# Hardware_Tutorial_-_Controller_Board_Int.net
KiCad netlist of a schematic drawn in Altium Designer
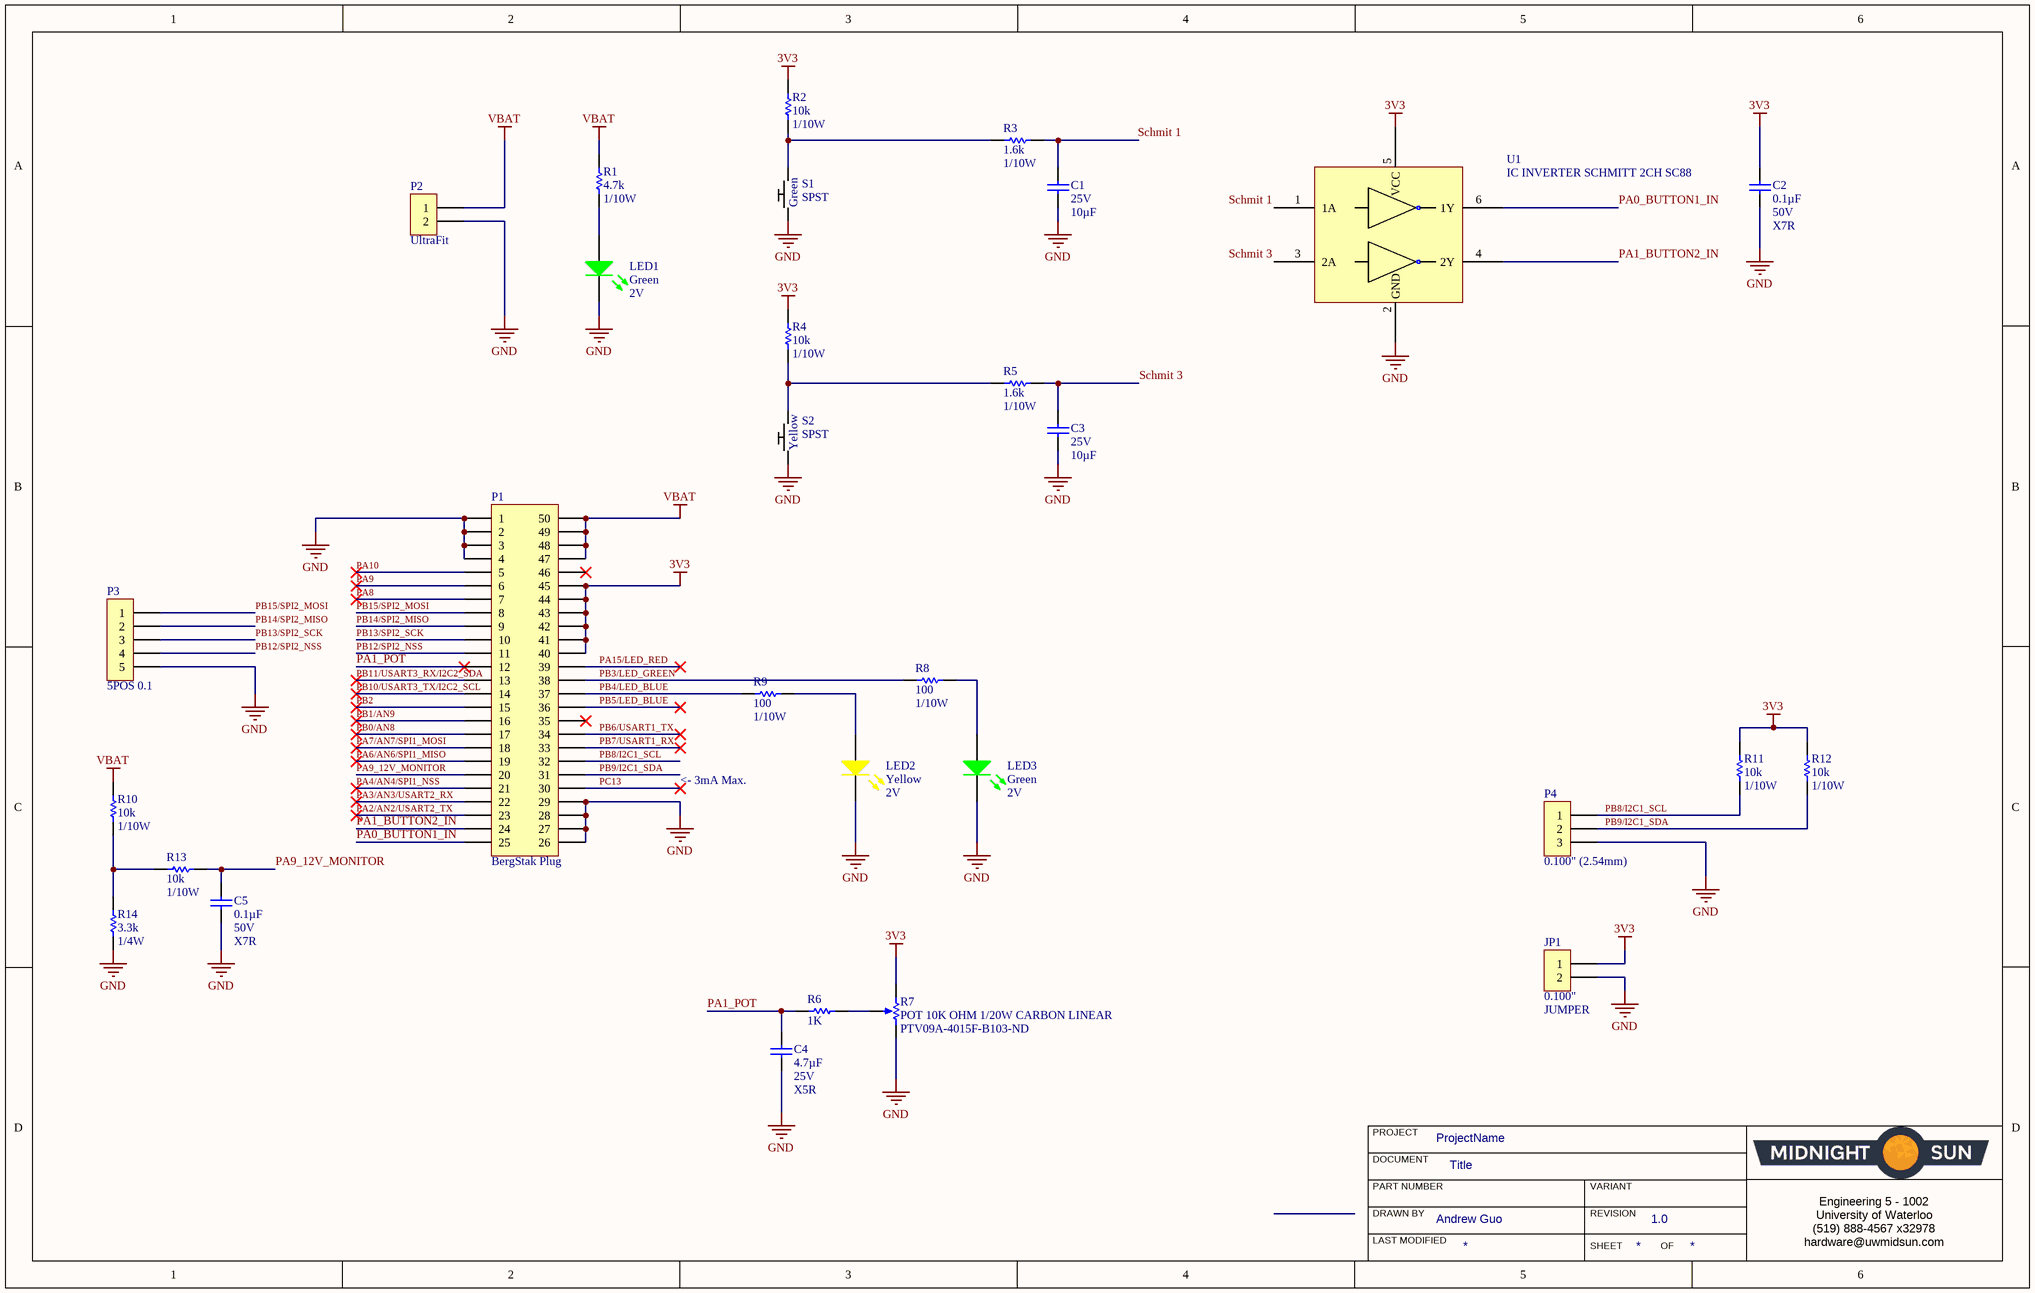
[diagram p0: Hardware Tutorial - Controller_Board_Interface.SchDoc]

(export (version "E")
  (design (tool "Eeschema 10.0.6"))
  (components
    (comp (ref "C1")
      (value "CAP CER 10uF 25V 10% X5R 0805")
      (footprint "CAP, 0805")
      (description "10µF ±10% 25V Ceramic Capacitor X5R 0805 (2012 Metric)")
      (fields
        (field (name "MANUFACTURER") "Murata Electronics North America")
        (field (name "MANUFACTURER PART NUMBER") "GRM21BR61E106KA73L")
        (field (name "VOLTAGE - RATED") "25V")
        (field (name "CAPACITANCE") "10µF")
      )
      (libsource (lib "Schematic Diagrams") (part "CAP CER 10uF 25V 10% X5R 0805"))
    )
    (comp (ref "C2")
      (value "CAP CER 0.1UF 50V 10% X7R 0603")
      (footprint "CAP, 0603")
      (description "0.10µF ±10% 50V Ceramic Capacitor X7R 0603 (1608 Metric)")
      (fields
        (field (name "TOLERANCE") "±10%")
        (field (name "CAPACITANCE") "0.1µF")
        (field (name "VOLTAGE") "50V")
        (field (name "TEMPERATURE COEFFICIENT") "X7R")
      )
      (libsource (lib "Schematic Diagrams") (part "CAP CER 0.1UF 50V 10% X7R 0603"))
    )
    (comp (ref "C3")
      (value "CAP CER 10uF 25V 10% X5R 0805")
      (footprint "CAP, 0805")
      (description "10µF ±10% 25V Ceramic Capacitor X5R 0805 (2012 Metric)")
      (fields
        (field (name "MANUFACTURER") "Murata Electronics North America")
        (field (name "MANUFACTURER PART NUMBER") "GRM21BR61E106KA73L")
        (field (name "VOLTAGE - RATED") "25V")
        (field (name "CAPACITANCE") "10µF")
      )
      (libsource (lib "Schematic Diagrams") (part "CAP CER 10uF 25V 10% X5R 0805"))
    )
    (comp (ref "C4")
      (value "CAP CER 4.7UF 25V 10% X5R 0603")
      (footprint "CAP, 0603")
      (description "4.7µF ±10% 25V Ceramic Capacitor X5R 0603 (1608 Metric)")
      (fields
        (field (name "TOLERANCE") "±10%")
        (field (name "CAPACITANCE") "4.7µF")
        (field (name "VOLTAGE") "25V")
        (field (name "TEMPERATURE COEFFICIENT") "X5R")
      )
      (libsource (lib "Schematic Diagrams") (part "CAP CER 4.7UF 25V 10% X5R 0603"))
    )
    (comp (ref "C5")
      (value "CAP CER 0.1UF 50V 10% X7R 0603")
      (footprint "CAP, 0603")
      (description "0.10µF ±10% 50V Ceramic Capacitor X7R 0603 (1608 Metric)")
      (fields
        (field (name "TOLERANCE") "±10%")
        (field (name "CAPACITANCE") "0.1µF")
        (field (name "VOLTAGE") "50V")
        (field (name "TEMPERATURE COEFFICIENT") "X7R")
      )
      (libsource (lib "Schematic Diagrams") (part "CAP CER 0.1UF 50V 10% X7R 0603"))
    )
    (comp (ref "JP1")
      (value "JUMPER")
      (footprint "CONN 2POS JUMPER 0.1\"")
      (description "2 Positions Header Connector Through Hole Gold")
      (fields
        (field (name "MANUFACTURER") "Omron Electronics Inc-EMC Div")
        (field (name "MANUFACTURER PART NUMBER") "XG8T-0231")
        (field (name "ROW SPACING - MATING") "0.100\"")
        (field (name "TYPE") "JUMPER")
      )
      (libsource (lib "Schematic Diagrams") (part "CONN 2POS JUMPER 0.1{dblquote}"))
    )
    (comp (ref "LED1")
      (value "LED GREEN CLEAR 2V 0603")
      (footprint "LED_0603")
      (description "Green 572nm LED Indication - Discrete 2V 0603 (1608 Metric)")
      (fields
        (field (name "MANUFACTURER") "Wurth Electronics Inc.")
        (field (name "MANUFACTURER PART NUMBER") "150060VS75000")
        (field (name "COLOR") "Green")
        (field (name "VOLTAGE - FORWARD (VF) (TYP)") "2V")
      )
      (libsource (lib "Schematic Diagrams") (part "LED GREEN CLEAR 2V 0603"))
    )
    (comp (ref "LED2")
      (value "LED YELLOW CLEAR 2.1V 0603")
      (footprint "LED_0603")
      (description "Yellow 590nm LED Indication - Discrete 2V 0603 (1608 Metric)")
      (fields
        (field (name "MANUFACTURER") "Wurth Electronics Inc.")
        (field (name "MANUFACTURER PART NUMBER") "150060YS75000")
        (field (name "COLOR") "Yellow")
        (field (name "VOLTAGE - FORWARD (VF) (TYP)") "2V")
      )
      (libsource (lib "Schematic Diagrams") (part "LED YELLOW CLEAR 2.1V 0603"))
    )
    (comp (ref "LED3")
      (value "LED GREEN CLEAR 2V 0603")
      (footprint "LED_0603")
      (description "Green 572nm LED Indication - Discrete 2V 0603 (1608 Metric)")
      (fields
        (field (name "MANUFACTURER") "Wurth Electronics Inc.")
        (field (name "MANUFACTURER PART NUMBER") "150060VS75000")
        (field (name "COLOR") "Green")
        (field (name "VOLTAGE - FORWARD (VF) (TYP)") "2V")
      )
      (libsource (lib "Schematic Diagrams") (part "LED GREEN CLEAR 2V 0603"))
    )
    (comp (ref "P1")
      (value "CONN 50POS Bergstak Plug 0.02\"")
      (footprint "CONN, Bergstak 50 Pos Plug")
      (description "50 Position Connector Plug, Outer Shroud Contacts Surface Mount Gold")
      (fields (field (name "SERIES") "BergStak Plug"))
      (libsource (lib "Schematic Diagrams") (part "CONN 50POS Bergstak Plug 0.02{dblquote}"))
    )
    (comp (ref "P2")
      (value "CONN 2POS ULTRA-FIT 0.138\"")
      (footprint "CONN, 2POS ULTRA-FIT")
      (description "Connector Header Through Hole 2 position 0.138\" (3.50mm)")
      (fields
        (field (name "MANUFACTURER") "Molex")
        (field (name "MANUFACTURER PART NUMBER") "1722871102")
        (field (name "SERIES") "UltraFit")
      )
      (libsource (lib "Schematic Diagrams") (part "CONN 2POS ULTRA-FIT 0.138{dblquote}"))
    )
    (comp (ref "P3")
      (value "5POS 0.1")
      (footprint "CONN, 5POS HEADR 0.1\"")
      (description "5 Positions Header, Breakaway Connector 0.100\" (2.54mm) Through Hole Tin")
      (libsource (lib "Schematic Diagrams") (part "CONN 5POS HEADR MALE 0.1in"))
    )
    (comp (ref "P4")
      (value "CONN 3POS HEADR MALE 0.1\"")
      (footprint "CONN, 3POS 0.100\" Header, 1 ROW")
      (description "3 Positions Header Connector 0.100\" (2.54mm) Through Hole Gold")
      (fields (field (name "VOLTAGE") "250V") (field (name "PITCH - MATING") "0.100\" (2.54mm)"))
      (libsource (lib "Schematic Diagrams") (part "CONN 3POS HEADR MALE 0.1{dblquote}"))
    )
    (comp (ref "R1")
      (value "RES 4.7K OHM 1% 1/10W 0603")
      (footprint "RES, 0603")
      (description "4.7k Ohm ±1% 0.1W, 1/10W Chip Resistor 0603 (1608 Metric) Moisture Resistant Thick Film")
      (fields
        (field (name "TOLERANCE") "±1%")
        (field (name "RESISTANCE (OHMS)") "4.7k")
        (field (name "POWER (WATTS)") "1/10W")
      )
      (libsource (lib "Schematic Diagrams") (part "RES 4.7K OHM 1% 1/10W 0603"))
    )
    (comp (ref "R2")
      (value "RES 191K OHM 1% 1/10W 0603")
      (footprint "RES, 0603")
      (description "191k Ohm ±1% 0.1W, 1/10W Chip Resistor 0603 (1608 Metric) Moisture Resistant Thick Film")
      (fields
        (field (name "TOLERANCE") "±1%")
        (field (name "RESISTANCE") "10k")
        (field (name "POWER") "1/10W")
      )
      (libsource (lib "Schematic Diagrams") (part "RES 191K OHM 1% 1/10W 0603"))
    )
    (comp (ref "R3")
      (value "RES 1.6K OHM 1% 1/10W 0603")
      (footprint "RES, 0603")
      (description "1.6 kOhms ±1% 0.1W, 1/10W Chip Resistor 0603 (1608 Metric) Moisture Resistant Thick Film")
      (fields
        (field (name "MANUFACTURER") "Yageo")
        (field (name "MANUFACTURER PART NUMBER") "RC0603FR-071K6L")
        (field (name "RESISTANCE") "1.6k")
        (field (name "POWER RATING") "1/10W")
      )
      (libsource (lib "Schematic Diagrams") (part "RES 1.6K OHM 1% 1/10W 0603"))
    )
    (comp (ref "R4")
      (value "RES 10K OHM 1% 1/10W 0603")
      (footprint "RES, 0603")
      (description "RES SMD 10K OHM 1% 1/10W 0603")
      (fields
        (field (name "TOLERANCE") "±1%")
        (field (name "RESISTANCE") "10k")
        (field (name "POWER") "1/10W")
      )
      (libsource (lib "Schematic Diagrams") (part "RES 10K OHM 1% 1/10W 0603"))
    )
    (comp (ref "R5")
      (value "RES 1.6K OHM 1% 1/10W 0603")
      (footprint "RES, 0603")
      (description "1.6 kOhms ±1% 0.1W, 1/10W Chip Resistor 0603 (1608 Metric) Moisture Resistant Thick Film")
      (fields
        (field (name "MANUFACTURER") "Yageo")
        (field (name "MANUFACTURER PART NUMBER") "RC0603FR-071K6L")
        (field (name "RESISTANCE") "1.6k")
        (field (name "POWER RATING") "1/10W")
      )
      (libsource (lib "Schematic Diagrams") (part "RES 1.6K OHM 1% 1/10W 0603"))
    )
    (comp (ref "R6")
      (value "1K")
      (footprint "RES, 0603")
      (description "1k Ohm ±5% 0.1W, 1/10W Chip Resistor 0603 (1608 Metric)")
      (fields
        (field (name "MANUFACTURER") "Yageo")
        (field (name "MANUFACTURER PART NUMBER") "RC0603JR-071KL")
      )
      (libsource (lib "Schematic Diagrams") (part "RES 1K OHM 5% 1/10W 0603"))
    )
    (comp (ref "R7")
      (value "POT 10K OHM 1/20W CARBON LINEAR")
      (footprint "POT footprint (tutorial)")
      (fields (field (name "SUPPLIER PART NUMBER 1") "PTV09A-4015F-B103-ND"))
      (libsource (lib "Schematic Diagrams") (part "POT 10K OHM 1/20W CARBON LINEAR"))
    )
    (comp (ref "R8")
      (value "RES 100 OHM 1% 1/10W 0603")
      (footprint "RES, 0603")
      (description "100 Ohm ±1% 0.1W, 1/10W Chip Resistor 0603 (1608 Metric) Moisture Resistant Thick Film")
      (fields
        (field (name "TOLERANCE") "±1%")
        (field (name "RESISTANCE") "100")
        (field (name "POWER") "1/10W")
      )
      (libsource (lib "Schematic Diagrams") (part "RES 100 OHM 1% 1/10W 0603"))
    )
    (comp (ref "R9")
      (value "RES 100 OHM 1% 1/10W 0603")
      (footprint "RES, 0603")
      (description "100 Ohm ±1% 0.1W, 1/10W Chip Resistor 0603 (1608 Metric) Moisture Resistant Thick Film")
      (fields
        (field (name "TOLERANCE") "±1%")
        (field (name "RESISTANCE") "100")
        (field (name "POWER") "1/10W")
      )
      (libsource (lib "Schematic Diagrams") (part "RES 100 OHM 1% 1/10W 0603"))
    )
    (comp (ref "R10")
      (value "RES 10K OHM 1% 1/10W 0603")
      (footprint "RES, 0603")
      (description "RES SMD 10K OHM 1% 1/10W 0603")
      (fields
        (field (name "TOLERANCE") "±1%")
        (field (name "RESISTANCE") "10k")
        (field (name "POWER") "1/10W")
      )
      (libsource (lib "Schematic Diagrams") (part "RES 10K OHM 1% 1/10W 0603"))
    )
    (comp (ref "R11")
      (value "RES 10K OHM 1% 1/10W 0603")
      (footprint "RES, 0603")
      (description "RES SMD 10K OHM 1% 1/10W 0603")
      (fields
        (field (name "TOLERANCE") "±1%")
        (field (name "RESISTANCE") "10k")
        (field (name "POWER") "1/10W")
      )
      (libsource (lib "Schematic Diagrams") (part "RES 10K OHM 1% 1/10W 0603"))
    )
    (comp (ref "R12")
      (value "RES 10K OHM 1% 1/10W 0603")
      (footprint "RES, 0603")
      (description "RES SMD 10K OHM 1% 1/10W 0603")
      (fields
        (field (name "TOLERANCE") "±1%")
        (field (name "RESISTANCE") "10k")
        (field (name "POWER") "1/10W")
      )
      (libsource (lib "Schematic Diagrams") (part "RES 10K OHM 1% 1/10W 0603"))
    )
    (comp (ref "R13")
      (value "RES 10K OHM 1% 1/10W 0603")
      (footprint "RES, 0603")
      (description "RES SMD 10K OHM 1% 1/10W 0603")
      (fields
        (field (name "TOLERANCE") "±1%")
        (field (name "RESISTANCE") "10k")
        (field (name "POWER") "1/10W")
      )
      (libsource (lib "Schematic Diagrams") (part "RES 10K OHM 1% 1/10W 0603"))
    )
    (comp (ref "R14")
      (value "RES 3.3K OHM 1% 1/4W 0603")
      (footprint "RES, 0603")
      (fields
        (field (name "TOLERANCE") "±1%")
        (field (name "RESISTANCE") "3.3k")
        (field (name "POWER") "1/4W")
      )
      (libsource (lib "Schematic Diagrams") (part "RES 3.3K OHM 1% 1/4W 0603"))
    )
    (comp (ref "S1")
      (value "SPST")
      (footprint "SW SPST D6 SERIES GREEN")
      (description "Pushbutton Switch SPST-NO Keyswitch Through Hole D6 Series Green")
      (fields (field (name "MANUFACTURER") "C&K") (field (name "MANUFACTURER PART NUMBER") "D6R50 F1 LFS"))
      (libsource (lib "Schematic Diagrams") (part "SW SPST-NO 0.1A 32V D6 Series Green"))
    )
    (comp (ref "S2")
      (value "SPST")
      (footprint "SW SPST D6 SERIES YELLOW")
      (description "Pushbutton Switch SPST-NO Keyswitch Through Hole D6 Series Yellow")
      (fields (field (name "MANUFACTURER") "C&K") (field (name "MANUFACTURER PART NUMBER") "D6R30 F1 LFS"))
      (libsource (lib "Schematic Diagrams") (part "SW SPST-NO 0.1A 32V D6 Series Yellow"))
    )
    (comp (ref "U1")
      (value "IC INVERTER SCHMITT 2CH SC88")
      (footprint "TSOP95P280X110-6N")
      (description "Inverter IC 2 Channel Schmitt Trigger SC-88")
      (libsource (lib "Schematic Diagrams") (part "IC INVERTER SCHMITT 2CH SC88"))
    )
  )
  (nets
    (net (code "1") (name "/PA0_BUTTON1_IN") (class "Default")
      (node (ref "P1") (pin "25") (pinfunction "25_25") (pintype "passive"))
      (node (ref "U1") (pin "6") (pinfunction "1Y_6") (pintype "passive"))
    )
    (net (code "2") (name "/PA1_BUTTON2_IN") (class "Default")
      (node (ref "P1") (pin "24") (pinfunction "24_24") (pintype "passive"))
      (node (ref "U1") (pin "4") (pinfunction "2Y_4") (pintype "passive"))
    )
    (net (code "3") (name "/PA1_POT") (class "Default")
      (node (ref "C4") (pin "1") (pinfunction "1_1") (pintype "passive"))
      (node (ref "P1") (pin "12") (pinfunction "12_12") (pintype "passive"))
      (node (ref "R6") (pin "1") (pinfunction "1_1") (pintype "passive"))
    )
    (net (code "4") (name "/PA2{slash}AN2{slash}USART2_TX") (class "Default")
      (node (ref "P1") (pin "23") (pinfunction "23_23") (pintype "passive+no_connect"))
    )
    (net (code "5") (name "/PA3{slash}AN3{slash}USART2_RX") (class "Default")
      (node (ref "P1") (pin "22") (pinfunction "22_22") (pintype "passive+no_connect"))
    )
    (net (code "6") (name "/PA4{slash}AN4{slash}SPI1_NSS") (class "Default")
      (node (ref "P1") (pin "21") (pinfunction "21_21") (pintype "passive+no_connect"))
    )
    (net (code "7") (name "/PA6{slash}AN6{slash}SPI1_MISO") (class "Default")
      (node (ref "P1") (pin "19") (pinfunction "19_19") (pintype "passive+no_connect"))
    )
    (net (code "8") (name "/PA7{slash}AN7{slash}SPI1_MOSI") (class "Default")
      (node (ref "P1") (pin "18") (pinfunction "18_18") (pintype "passive+no_connect"))
    )
    (net (code "9") (name "/PA8") (class "Default")
      (node (ref "P1") (pin "7") (pinfunction "7_7") (pintype "passive+no_connect"))
    )
    (net (code "10") (name "/PA9") (class "Default")
      (node (ref "P1") (pin "6") (pinfunction "6_6") (pintype "passive+no_connect"))
    )
    (net (code "11") (name "/PA9_12V_MONITOR") (class "Default")
      (node (ref "C5") (pin "1") (pinfunction "1_1") (pintype "passive"))
      (node (ref "P1") (pin "20") (pinfunction "20_20") (pintype "passive"))
      (node (ref "R13") (pin "2") (pinfunction "2_2") (pintype "passive"))
    )
    (net (code "12") (name "/PA10") (class "Default")
      (node (ref "P1") (pin "5") (pinfunction "5_5") (pintype "passive+no_connect"))
    )
    (net (code "13") (name "/PA15{slash}LED_RED") (class "Default")
      (node (ref "P1") (pin "39") (pinfunction "39_39") (pintype "passive+no_connect"))
    )
    (net (code "14") (name "/PB0{slash}AN8") (class "Default")
      (node (ref "P1") (pin "17") (pinfunction "17_17") (pintype "passive+no_connect"))
    )
    (net (code "15") (name "/PB1{slash}AN9") (class "Default")
      (node (ref "P1") (pin "16") (pinfunction "16_16") (pintype "passive+no_connect"))
    )
    (net (code "16") (name "/PB2") (class "Default")
      (node (ref "P1") (pin "15") (pinfunction "15_15") (pintype "passive+no_connect"))
    )
    (net (code "17") (name "/PB3{slash}LED_GREEN") (class "Default")
      (node (ref "P1") (pin "38") (pinfunction "38_38") (pintype "passive"))
      (node (ref "R8") (pin "1") (pinfunction "1_1") (pintype "passive"))
    )
    (net (code "18") (name "/PB4{slash}LED_BLUE") (class "Default")
      (node (ref "P1") (pin "37") (pinfunction "37_37") (pintype "passive"))
      (node (ref "R9") (pin "1") (pinfunction "1_1") (pintype "passive"))
    )
    (net (code "19") (name "/PB5{slash}LED_BLUE") (class "Default")
      (node (ref "P1") (pin "36") (pinfunction "36_36") (pintype "passive+no_connect"))
    )
    (net (code "20") (name "/PB6{slash}USART1_TX") (class "Default")
      (node (ref "P1") (pin "34") (pinfunction "34_34") (pintype "passive+no_connect"))
    )
    (net (code "21") (name "/PB7{slash}USART1_RX") (class "Default")
      (node (ref "P1") (pin "33") (pinfunction "33_33") (pintype "passive+no_connect"))
    )
    (net (code "22") (name "/PB8{slash}I2C1_SCL") (class "Default")
      (node (ref "P1") (pin "32") (pinfunction "32_32") (pintype "passive"))
      (node (ref "P4") (pin "1") (pinfunction "1_1") (pintype "passive"))
      (node (ref "R11") (pin "2") (pinfunction "2_2") (pintype "passive"))
    )
    (net (code "23") (name "/PB9{slash}I2C1_SDA") (class "Default")
      (node (ref "P1") (pin "31") (pinfunction "31_31") (pintype "passive"))
      (node (ref "P4") (pin "2") (pinfunction "2_2") (pintype "passive"))
      (node (ref "R12") (pin "2") (pinfunction "2_2") (pintype "passive"))
    )
    (net (code "24") (name "/PB10{slash}USART3_TX{slash}I2C2_SCL") (class "Default")
      (node (ref "P1") (pin "14") (pinfunction "14_14") (pintype "passive+no_connect"))
    )
    (net (code "25") (name "/PB11{slash}USART3_RX{slash}I2C2_SDA") (class "Default")
      (node (ref "P1") (pin "13") (pinfunction "13_13") (pintype "passive+no_connect"))
    )
    (net (code "26") (name "/PB12{slash}SPI2_NSS") (class "Default")
      (node (ref "P1") (pin "11") (pinfunction "11_11") (pintype "passive"))
      (node (ref "P3") (pin "4") (pinfunction "4_4") (pintype "passive"))
    )
    (net (code "27") (name "/PB13{slash}SPI2_SCK") (class "Default")
      (node (ref "P1") (pin "10") (pinfunction "10_10") (pintype "passive"))
      (node (ref "P3") (pin "3") (pinfunction "3_3") (pintype "passive"))
    )
    (net (code "28") (name "/PB14{slash}SPI2_MISO") (class "Default")
      (node (ref "P1") (pin "9") (pinfunction "9_9") (pintype "passive"))
      (node (ref "P3") (pin "2") (pinfunction "2_2") (pintype "passive"))
    )
    (net (code "29") (name "/PB15{slash}SPI2_MOSI") (class "Default")
      (node (ref "P1") (pin "8") (pinfunction "8_8") (pintype "passive"))
      (node (ref "P3") (pin "1") (pinfunction "1_1") (pintype "passive"))
    )
    (net (code "30") (name "/PC13") (class "Default")
      (node (ref "P1") (pin "30") (pinfunction "30_30") (pintype "passive+no_connect"))
    )
    (net (code "31") (name "/Schmit 1") (class "Default")
      (node (ref "C1") (pin "1") (pinfunction "1_1") (pintype "passive"))
      (node (ref "R3") (pin "2") (pinfunction "2_2") (pintype "passive"))
      (node (ref "U1") (pin "1") (pinfunction "1A_1") (pintype "passive"))
    )
    (net (code "32") (name "/Schmit 3") (class "Default")
      (node (ref "C3") (pin "1") (pinfunction "1_1") (pintype "passive"))
      (node (ref "R5") (pin "2") (pinfunction "2_2") (pintype "passive"))
      (node (ref "U1") (pin "3") (pinfunction "2A_3") (pintype "passive"))
    )
    (net (code "33") (name "3V3") (class "Default")
      (node (ref "C2") (pin "1") (pinfunction "1_1") (pintype "passive"))
      (node (ref "JP1") (pin "1") (pinfunction "1_1") (pintype "passive"))
      (node (ref "P1") (pin "40") (pinfunction "40_40") (pintype "passive"))
      (node (ref "P1") (pin "41") (pinfunction "41_41") (pintype "passive"))
      (node (ref "P1") (pin "42") (pinfunction "42_42") (pintype "passive"))
      (node (ref "P1") (pin "43") (pinfunction "43_43") (pintype "passive"))
      (node (ref "P1") (pin "44") (pinfunction "44_44") (pintype "passive"))
      (node (ref "P1") (pin "45") (pinfunction "45_45") (pintype "passive"))
      (node (ref "R11") (pin "1") (pinfunction "1_1") (pintype "passive"))
      (node (ref "R12") (pin "1") (pinfunction "1_1") (pintype "passive"))
      (node (ref "R2") (pin "1") (pinfunction "1_1") (pintype "passive"))
      (node (ref "R4") (pin "1") (pinfunction "1_1") (pintype "passive"))
      (node (ref "R7") (pin "1") (pinfunction "TOP_1") (pintype "passive"))
      (node (ref "U1") (pin "5") (pinfunction "VCC_5") (pintype "passive"))
    )
    (net (code "34") (name "GND") (class "Default")
      (node (ref "C1") (pin "2") (pinfunction "2_2") (pintype "passive"))
      (node (ref "C2") (pin "2") (pinfunction "2_2") (pintype "passive"))
      (node (ref "C3") (pin "2") (pinfunction "2_2") (pintype "passive"))
      (node (ref "C4") (pin "2") (pinfunction "2_2") (pintype "passive"))
      (node (ref "C5") (pin "2") (pinfunction "2_2") (pintype "passive"))
      (node (ref "JP1") (pin "2") (pinfunction "2_2") (pintype "passive"))
      (node (ref "LED1") (pin "2") (pinfunction "K_2") (pintype "passive"))
      (node (ref "LED2") (pin "2") (pinfunction "K_2") (pintype "passive"))
      (node (ref "LED3") (pin "2") (pinfunction "K_2") (pintype "passive"))
      (node (ref "P1") (pin "1") (pinfunction "1_1") (pintype "passive"))
      (node (ref "P1") (pin "2") (pinfunction "2_2") (pintype "passive"))
      (node (ref "P1") (pin "26") (pinfunction "26_26") (pintype "passive"))
      (node (ref "P1") (pin "27") (pinfunction "27_27") (pintype "passive"))
      (node (ref "P1") (pin "28") (pinfunction "28_28") (pintype "passive"))
      (node (ref "P1") (pin "29") (pinfunction "29_29") (pintype "passive"))
      (node (ref "P1") (pin "3") (pinfunction "3_3") (pintype "passive"))
      (node (ref "P1") (pin "4") (pinfunction "4_4") (pintype "passive"))
      (node (ref "P2") (pin "2") (pinfunction "2_2") (pintype "passive"))
      (node (ref "P3") (pin "5") (pinfunction "5_5") (pintype "passive"))
      (node (ref "P4") (pin "3") (pinfunction "3_3") (pintype "passive"))
      (node (ref "R14") (pin "2") (pinfunction "2_2") (pintype "passive"))
      (node (ref "R7") (pin "3") (pinfunction "BOT_3") (pintype "passive"))
      (node (ref "S1") (pin "1") (pinfunction "1_1") (pintype "passive"))
      (node (ref "S2") (pin "1") (pinfunction "1_1") (pintype "passive"))
      (node (ref "U1") (pin "2") (pinfunction "GND_2") (pintype "passive"))
    )
    (net (code "35") (name "Net-(LED1-A)") (class "Default")
      (node (ref "LED1") (pin "1") (pinfunction "A_1") (pintype "passive"))
      (node (ref "R1") (pin "2") (pinfunction "2_2") (pintype "passive"))
    )
    (net (code "36") (name "Net-(LED2-A)") (class "Default")
      (node (ref "LED2") (pin "1") (pinfunction "A_1") (pintype "passive"))
      (node (ref "R9") (pin "2") (pinfunction "2_2") (pintype "passive"))
    )
    (net (code "37") (name "Net-(LED3-A)") (class "Default")
      (node (ref "LED3") (pin "1") (pinfunction "A_1") (pintype "passive"))
      (node (ref "R8") (pin "2") (pinfunction "2_2") (pintype "passive"))
    )
    (net (code "38") (name "Net-(R2-Pad2)") (class "Default")
      (node (ref "R2") (pin "2") (pinfunction "2_2") (pintype "passive"))
      (node (ref "R3") (pin "1") (pinfunction "1_1") (pintype "passive"))
      (node (ref "S1") (pin "2") (pinfunction "2_2") (pintype "passive"))
    )
    (net (code "39") (name "Net-(R4-Pad2)") (class "Default")
      (node (ref "R4") (pin "2") (pinfunction "2_2") (pintype "passive"))
      (node (ref "R5") (pin "1") (pinfunction "1_1") (pintype "passive"))
      (node (ref "S2") (pin "2") (pinfunction "2_2") (pintype "passive"))
    )
    (net (code "40") (name "Net-(R7-TAP)") (class "Default")
      (node (ref "R6") (pin "2") (pinfunction "2_2") (pintype "passive"))
      (node (ref "R7") (pin "2") (pinfunction "TAP_2") (pintype "passive"))
    )
    (net (code "41") (name "Net-(R10-Pad2)") (class "Default")
      (node (ref "R10") (pin "2") (pinfunction "2_2") (pintype "passive"))
      (node (ref "R13") (pin "1") (pinfunction "1_1") (pintype "passive"))
      (node (ref "R14") (pin "1") (pinfunction "1_1") (pintype "passive"))
    )
    (net (code "42") (name "VBAT") (class "Default")
      (node (ref "P1") (pin "47") (pinfunction "47_47") (pintype "passive"))
      (node (ref "P1") (pin "48") (pinfunction "48_48") (pintype "passive"))
      (node (ref "P1") (pin "49") (pinfunction "49_49") (pintype "passive"))
      (node (ref "P1") (pin "50") (pinfunction "50_50") (pintype "passive"))
      (node (ref "P2") (pin "1") (pinfunction "1_1") (pintype "passive"))
      (node (ref "R1") (pin "1") (pinfunction "1_1") (pintype "passive"))
      (node (ref "R10") (pin "1") (pinfunction "1_1") (pintype "passive"))
    )
    (net (code "43") (name "unconnected-(P1-Pad35)") (class "Default")
      (node (ref "P1") (pin "35") (pinfunction "35_35") (pintype "passive+no_connect"))
    )
    (net (code "44") (name "unconnected-(P1-Pad46)") (class "Default")
      (node (ref "P1") (pin "46") (pinfunction "46_46") (pintype "passive+no_connect"))
    )
  )
)
